# picostepknobs.net
KiCad netlist of a schematic drawn in EAGLE
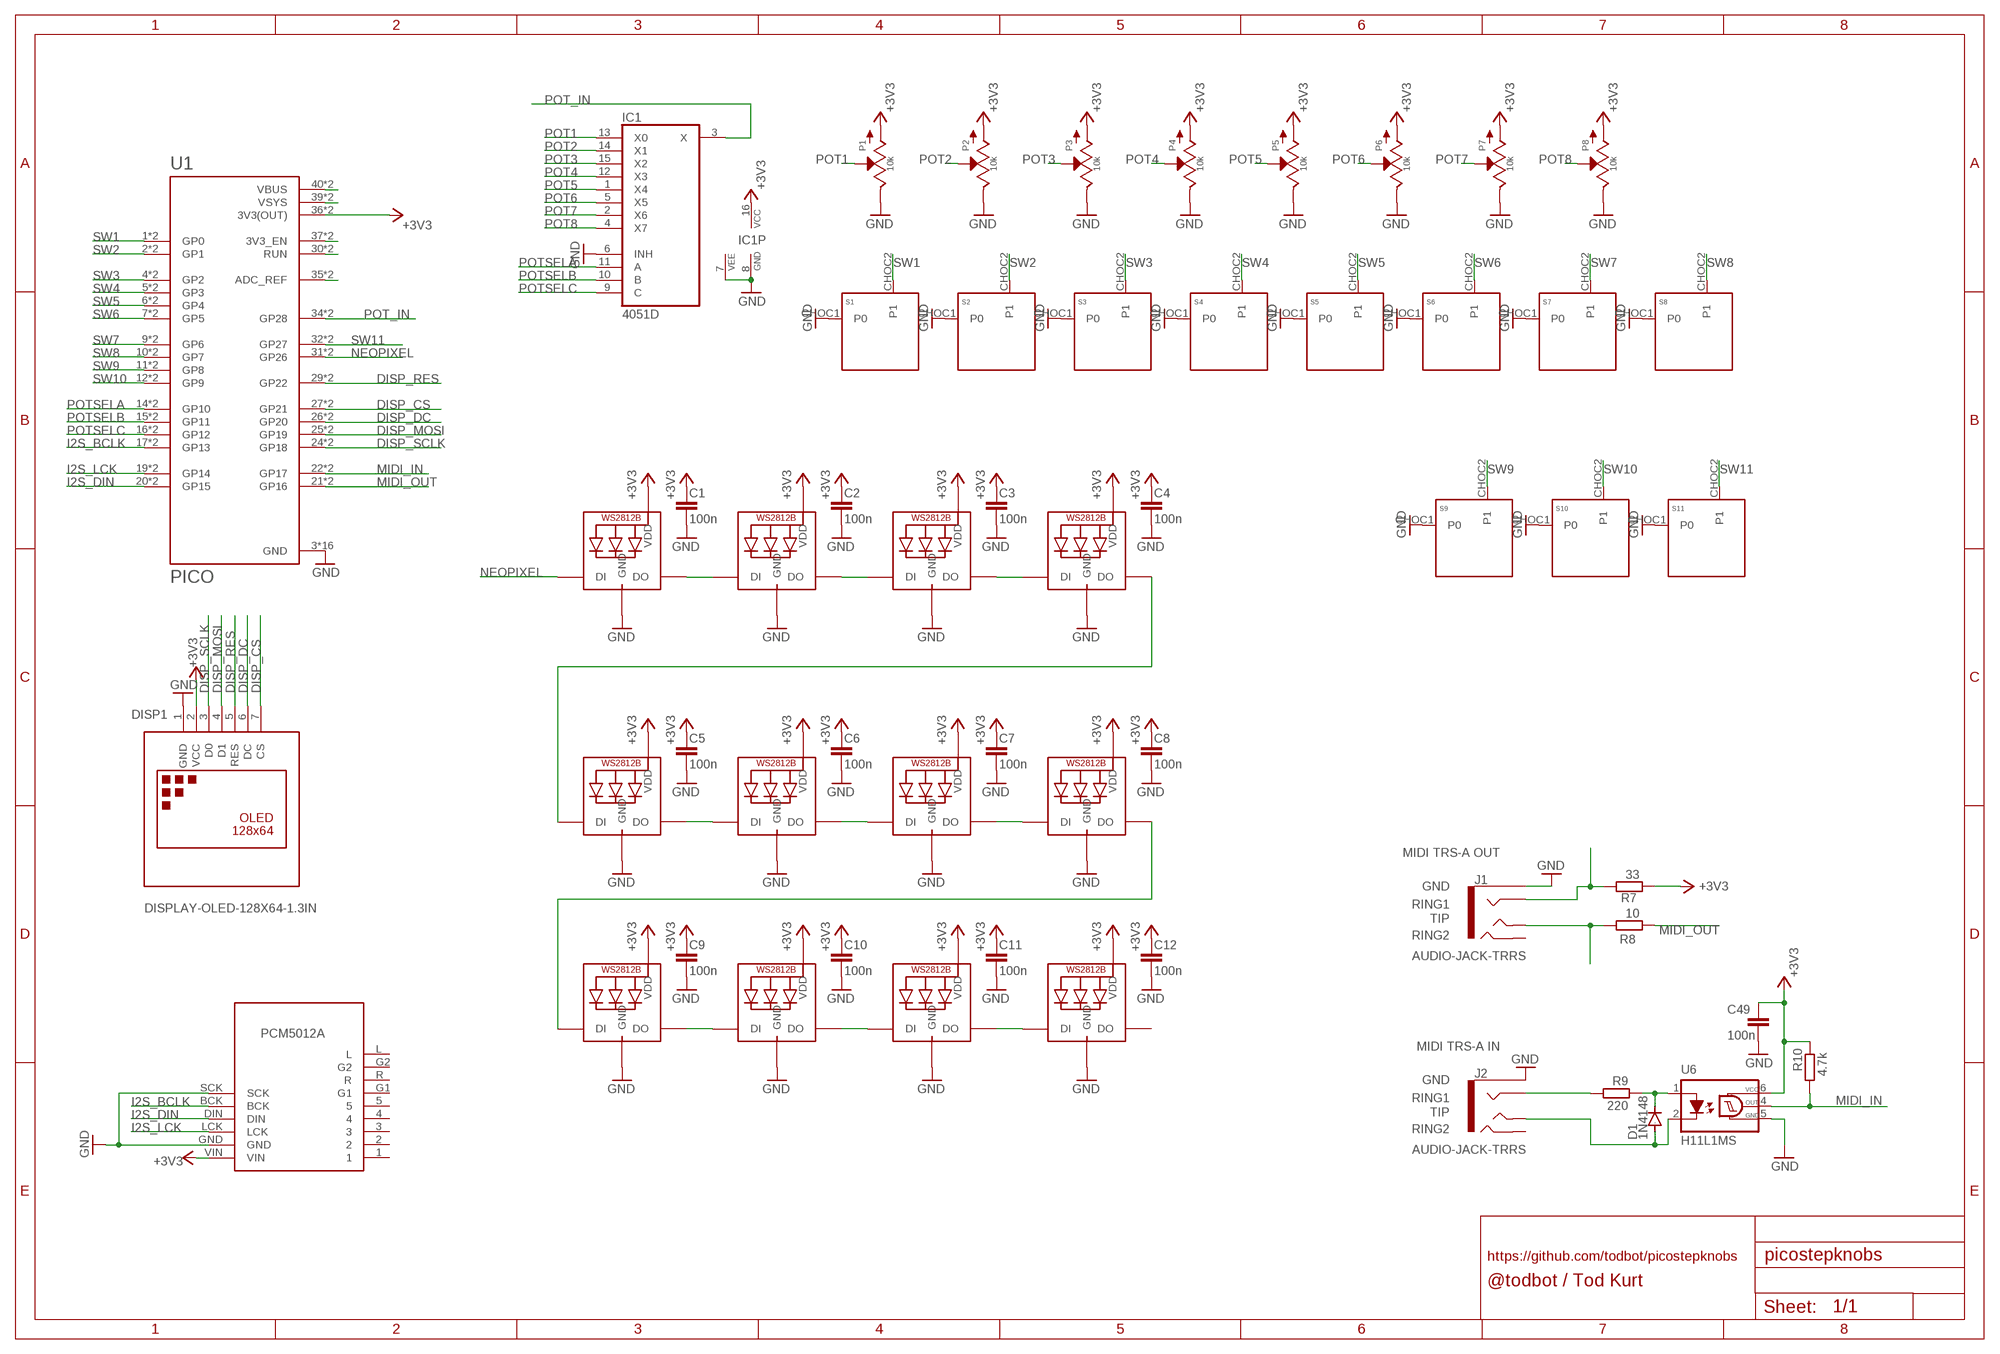
[diagram p0: schematic, sheet 1]

(export (version "E")
  (design (tool "Eeschema 10.0.6"))
  (components
    (comp (ref "C1")
      (value "100n")
      (footprint "eagle-import:C0805")
      (libsource (lib "eagle-import") (part "C-EUC0805"))
    )
    (comp (ref "C2")
      (value "100n")
      (footprint "eagle-import:C0805")
      (libsource (lib "eagle-import") (part "C-EUC0805"))
    )
    (comp (ref "C3")
      (value "100n")
      (footprint "eagle-import:C0805")
      (libsource (lib "eagle-import") (part "C-EUC0805"))
    )
    (comp (ref "C4")
      (value "100n")
      (footprint "eagle-import:C0805")
      (libsource (lib "eagle-import") (part "C-EUC0805"))
    )
    (comp (ref "C5")
      (value "100n")
      (footprint "eagle-import:C0805")
      (libsource (lib "eagle-import") (part "C-EUC0805"))
    )
    (comp (ref "C6")
      (value "100n")
      (footprint "eagle-import:C0805")
      (libsource (lib "eagle-import") (part "C-EUC0805"))
    )
    (comp (ref "C7")
      (value "100n")
      (footprint "eagle-import:C0805")
      (libsource (lib "eagle-import") (part "C-EUC0805"))
    )
    (comp (ref "C8")
      (value "100n")
      (footprint "eagle-import:C0805")
      (libsource (lib "eagle-import") (part "C-EUC0805"))
    )
    (comp (ref "C9")
      (value "100n")
      (footprint "eagle-import:C0805")
      (libsource (lib "eagle-import") (part "C-EUC0805"))
    )
    (comp (ref "C10")
      (value "100n")
      (footprint "eagle-import:C0805")
      (libsource (lib "eagle-import") (part "C-EUC0805"))
    )
    (comp (ref "C11")
      (value "100n")
      (footprint "eagle-import:C0805")
      (libsource (lib "eagle-import") (part "C-EUC0805"))
    )
    (comp (ref "C12")
      (value "100n")
      (footprint "eagle-import:C0805")
      (libsource (lib "eagle-import") (part "C-EUC0805"))
    )
    (comp (ref "C49")
      (value "100n")
      (footprint "eagle-import:C0805")
      (libsource (lib "eagle-import") (part "C-EUC0805"))
    )
    (comp (ref "D1")
      (value "1N4148")
      (footprint "eagle-import:SOD123")
      (libsource (lib "eagle-import") (part "DIODE-SOD123"))
    )
    (comp (ref "DISP1")
      (value "DISPLAY-OLED-128X64-1.3IN")
      (footprint "eagle-import:DISPLAY-OLED-128X64-1.3IN")
      (libsource (lib "eagle-import") (part "DISPLAY-OLED-128X64-1.3IN"))
    )
    (comp (ref "IC1")
      (value "4051D")
      (footprint "eagle-import:SO16")
      (libsource (lib "eagle-import") (part "4051D"))
    )
    (comp (ref "J1")
      (value "AUDIO-JACK-TRRS")
      (footprint "eagle-import:PJ-320D_SPARKFUN")
      (fields (field (name "MPN") "PJ-320D") (field (name "LCSC") "C431535"))
      (libsource (lib "eagle-import") (part "AUDIO-JACK-TRRS"))
    )
    (comp (ref "J2")
      (value "AUDIO-JACK-TRRS")
      (footprint "eagle-import:PJ-320D_SPARKFUN")
      (fields (field (name "MPN") "PJ-320D"))
      (libsource (lib "eagle-import") (part "AUDIO-JACK-TRRS"))
    )
    (comp (ref "LED1")
      (value "WS2812B3535")
      (footprint "eagle-import:LED3535")
      (libsource (lib "eagle-import") (part "WS2812B3535"))
    )
    (comp (ref "LED2")
      (value "WS2812B3535")
      (footprint "eagle-import:LED3535")
      (libsource (lib "eagle-import") (part "WS2812B3535"))
    )
    (comp (ref "LED3")
      (value "WS2812B3535")
      (footprint "eagle-import:LED3535")
      (libsource (lib "eagle-import") (part "WS2812B3535"))
    )
    (comp (ref "LED4")
      (value "WS2812B3535")
      (footprint "eagle-import:LED3535")
      (libsource (lib "eagle-import") (part "WS2812B3535"))
    )
    (comp (ref "LED5")
      (value "WS2812B3535")
      (footprint "eagle-import:LED3535")
      (libsource (lib "eagle-import") (part "WS2812B3535"))
    )
    (comp (ref "LED6")
      (value "WS2812B3535")
      (footprint "eagle-import:LED3535")
      (libsource (lib "eagle-import") (part "WS2812B3535"))
    )
    (comp (ref "LED7")
      (value "WS2812B3535")
      (footprint "eagle-import:LED3535")
      (libsource (lib "eagle-import") (part "WS2812B3535"))
    )
    (comp (ref "LED8")
      (value "WS2812B3535")
      (footprint "eagle-import:LED3535")
      (libsource (lib "eagle-import") (part "WS2812B3535"))
    )
    (comp (ref "LED9")
      (value "WS2812B3535")
      (footprint "eagle-import:LED3535")
      (libsource (lib "eagle-import") (part "WS2812B3535"))
    )
    (comp (ref "LED10")
      (value "WS2812B3535")
      (footprint "eagle-import:LED3535")
      (libsource (lib "eagle-import") (part "WS2812B3535"))
    )
    (comp (ref "LED11")
      (value "WS2812B3535")
      (footprint "eagle-import:LED3535")
      (libsource (lib "eagle-import") (part "WS2812B3535"))
    )
    (comp (ref "LED12")
      (value "WS2812B3535")
      (footprint "eagle-import:LED3535")
      (libsource (lib "eagle-import") (part "WS2812B3535"))
    )
    (comp (ref "P1")
      (value "10k")
      (footprint "eagle-import:OG-POTS_ALPS_POT_VERTICAL_WITHBIGKNOB")
      (libsource (lib "eagle-import") (part "POTZEPHPOT_BIGKNOB"))
    )
    (comp (ref "P2")
      (value "10k")
      (footprint "eagle-import:OG-POTS_ALPS_POT_VERTICAL_WITHBIGKNOB")
      (libsource (lib "eagle-import") (part "POTZEPHPOT_BIGKNOB"))
    )
    (comp (ref "P3")
      (value "10k")
      (footprint "eagle-import:OG-POTS_ALPS_POT_VERTICAL_WITHBIGKNOB")
      (libsource (lib "eagle-import") (part "POTZEPHPOT_BIGKNOB"))
    )
    (comp (ref "P4")
      (value "10k")
      (footprint "eagle-import:OG-POTS_ALPS_POT_VERTICAL_WITHBIGKNOB")
      (libsource (lib "eagle-import") (part "POTZEPHPOT_BIGKNOB"))
    )
    (comp (ref "P5")
      (value "10k")
      (footprint "eagle-import:OG-POTS_ALPS_POT_VERTICAL_WITHBIGKNOB")
      (libsource (lib "eagle-import") (part "POTZEPHPOT_BIGKNOB"))
    )
    (comp (ref "P6")
      (value "10k")
      (footprint "eagle-import:OG-POTS_ALPS_POT_VERTICAL_WITHBIGKNOB")
      (libsource (lib "eagle-import") (part "POTZEPHPOT_BIGKNOB"))
    )
    (comp (ref "P7")
      (value "10k")
      (footprint "eagle-import:OG-POTS_ALPS_POT_VERTICAL_WITHBIGKNOB")
      (libsource (lib "eagle-import") (part "POTZEPHPOT_BIGKNOB"))
    )
    (comp (ref "P8")
      (value "10k")
      (footprint "eagle-import:OG-POTS_ALPS_POT_VERTICAL_WITHBIGKNOB")
      (libsource (lib "eagle-import") (part "POTZEPHPOT_BIGKNOB"))
    )
    (comp (ref "PCM5102A")
      (value "I2S_PCM_51XX_SOUNDCARD")
      (footprint "eagle-import:I2S_PCM_5100_SOUNDCARD")
      (libsource (lib "eagle-import") (part "I2S_PCM_51XX_SOUNDCARD"))
    )
    (comp (ref "R7")
      (value "33")
      (footprint "eagle-import:R0805")
      (libsource (lib "eagle-import") (part "R-EU_R0805"))
    )
    (comp (ref "R8")
      (value "10")
      (footprint "eagle-import:R0805")
      (libsource (lib "eagle-import") (part "R-EU_R0805"))
    )
    (comp (ref "R9")
      (value "220")
      (footprint "eagle-import:R0805")
      (libsource (lib "eagle-import") (part "R-EU_R0805"))
    )
    (comp (ref "R10")
      (value "4.7k")
      (footprint "eagle-import:R0805")
      (libsource (lib "eagle-import") (part "R-EU_R0805"))
    )
    (comp (ref "S1")
      (value "KEYSWITCH-PLAIN-CHOC-1U")
      (footprint "eagle-import:CHOC-1U")
      (libsource (lib "eagle-import") (part "KEYSWITCH-PLAIN-CHOC-1U"))
    )
    (comp (ref "S2")
      (value "KEYSWITCH-PLAIN-CHOC-1U")
      (footprint "eagle-import:CHOC-1U")
      (libsource (lib "eagle-import") (part "KEYSWITCH-PLAIN-CHOC-1U"))
    )
    (comp (ref "S3")
      (value "KEYSWITCH-PLAIN-CHOC-1U")
      (footprint "eagle-import:CHOC-1U")
      (libsource (lib "eagle-import") (part "KEYSWITCH-PLAIN-CHOC-1U"))
    )
    (comp (ref "S4")
      (value "KEYSWITCH-PLAIN-CHOC-1U")
      (footprint "eagle-import:CHOC-1U")
      (libsource (lib "eagle-import") (part "KEYSWITCH-PLAIN-CHOC-1U"))
    )
    (comp (ref "S5")
      (value "KEYSWITCH-PLAIN-CHOC-1U")
      (footprint "eagle-import:CHOC-1U")
      (libsource (lib "eagle-import") (part "KEYSWITCH-PLAIN-CHOC-1U"))
    )
    (comp (ref "S6")
      (value "KEYSWITCH-PLAIN-CHOC-1U")
      (footprint "eagle-import:CHOC-1U")
      (libsource (lib "eagle-import") (part "KEYSWITCH-PLAIN-CHOC-1U"))
    )
    (comp (ref "S7")
      (value "KEYSWITCH-PLAIN-CHOC-1U")
      (footprint "eagle-import:CHOC-1U")
      (libsource (lib "eagle-import") (part "KEYSWITCH-PLAIN-CHOC-1U"))
    )
    (comp (ref "S8")
      (value "KEYSWITCH-PLAIN-CHOC-1U")
      (footprint "eagle-import:CHOC-1U")
      (libsource (lib "eagle-import") (part "KEYSWITCH-PLAIN-CHOC-1U"))
    )
    (comp (ref "S9")
      (value "KEYSWITCH-PLAIN-CHOC-1U")
      (footprint "eagle-import:CHOC-1U")
      (libsource (lib "eagle-import") (part "KEYSWITCH-PLAIN-CHOC-1U"))
    )
    (comp (ref "S10")
      (value "KEYSWITCH-PLAIN-CHOC-1U")
      (footprint "eagle-import:CHOC-1U")
      (libsource (lib "eagle-import") (part "KEYSWITCH-PLAIN-CHOC-1U"))
    )
    (comp (ref "S11")
      (value "KEYSWITCH-PLAIN-CHOC-1U")
      (footprint "eagle-import:CHOC-1U")
      (libsource (lib "eagle-import") (part "KEYSWITCH-PLAIN-CHOC-1U"))
    )
    (comp (ref "U1")
      (value "PICO")
      (footprint "eagle-import:PICO-PKG-NO_DEBUG")
      (libsource (lib "eagle-import") (part "RASPBERRY_PICO-NO_DEBUG"))
    )
    (comp (ref "U6")
      (value "H11L1MS")
      (footprint "eagle-import:DIL6-SMD")
      (libsource (lib "eagle-import") (part "H11LMS1"))
    )
  )
  (nets
    (net (code "1") (name "+3V3") (class "Default")
      (node (ref "C1") (pin "1") (pinfunction "1_1") (pintype "passive"))
      (node (ref "C10") (pin "1") (pinfunction "1_1") (pintype "passive"))
      (node (ref "C11") (pin "1") (pinfunction "1_1") (pintype "passive"))
      (node (ref "C12") (pin "1") (pinfunction "1_1") (pintype "passive"))
      (node (ref "C2") (pin "1") (pinfunction "1_1") (pintype "passive"))
      (node (ref "C3") (pin "1") (pinfunction "1_1") (pintype "passive"))
      (node (ref "C4") (pin "1") (pinfunction "1_1") (pintype "passive"))
      (node (ref "C49") (pin "1") (pinfunction "1_1") (pintype "passive"))
      (node (ref "C5") (pin "1") (pinfunction "1_1") (pintype "passive"))
      (node (ref "C6") (pin "1") (pinfunction "1_1") (pintype "passive"))
      (node (ref "C7") (pin "1") (pinfunction "1_1") (pintype "passive"))
      (node (ref "C8") (pin "1") (pinfunction "1_1") (pintype "passive"))
      (node (ref "C9") (pin "1") (pinfunction "1_1") (pintype "passive"))
      (node (ref "DISP1") (pin "2") (pinfunction "VCC_2") (pintype "power_in"))
      (node (ref "IC1") (pin "16") (pinfunction "VCC_16") (pintype "power_in"))
      (node (ref "LED1") (pin "2") (pinfunction "VDD_2") (pintype "power_in"))
      (node (ref "LED10") (pin "2") (pinfunction "VDD_2") (pintype "power_in"))
      (node (ref "LED11") (pin "2") (pinfunction "VDD_2") (pintype "power_in"))
      (node (ref "LED12") (pin "2") (pinfunction "VDD_2") (pintype "power_in"))
      (node (ref "LED2") (pin "2") (pinfunction "VDD_2") (pintype "power_in"))
      (node (ref "LED3") (pin "2") (pinfunction "VDD_2") (pintype "power_in"))
      (node (ref "LED4") (pin "2") (pinfunction "VDD_2") (pintype "power_in"))
      (node (ref "LED5") (pin "2") (pinfunction "VDD_2") (pintype "power_in"))
      (node (ref "LED6") (pin "2") (pinfunction "VDD_2") (pintype "power_in"))
      (node (ref "LED7") (pin "2") (pinfunction "VDD_2") (pintype "power_in"))
      (node (ref "LED8") (pin "2") (pinfunction "VDD_2") (pintype "power_in"))
      (node (ref "LED9") (pin "2") (pinfunction "VDD_2") (pintype "power_in"))
      (node (ref "P1") (pin "P$3") (pinfunction "A_P$3") (pintype "passive"))
      (node (ref "P2") (pin "P$3") (pinfunction "A_P$3") (pintype "passive"))
      (node (ref "P3") (pin "P$3") (pinfunction "A_P$3") (pintype "passive"))
      (node (ref "P4") (pin "P$3") (pinfunction "A_P$3") (pintype "passive"))
      (node (ref "P5") (pin "P$3") (pinfunction "A_P$3") (pintype "passive"))
      (node (ref "P6") (pin "P$3") (pinfunction "A_P$3") (pintype "passive"))
      (node (ref "P7") (pin "P$3") (pinfunction "A_P$3") (pintype "passive"))
      (node (ref "P8") (pin "P$3") (pinfunction "A_P$3") (pintype "passive"))
      (node (ref "PCM5102A") (pin "VIN") (pinfunction "VIN_VIN") (pintype "bidirectional"))
      (node (ref "R10") (pin "1") (pinfunction "1_1") (pintype "passive"))
      (node (ref "R7") (pin "2") (pinfunction "2_2") (pintype "passive"))
      (node (ref "U1") (pin "36") (pinfunction "3V3(OUT)_36") (pintype "power_in"))
      (node (ref "U1") (pin "P$36") (pinfunction "3V3(OUT)_P$36") (pintype "power_in"))
      (node (ref "U6") (pin "6") (pinfunction "VCC_6") (pintype "power_in"))
    )
    (net (code "2") (name "/DISP_CS") (class "Default")
      (node (ref "DISP1") (pin "7") (pinfunction "CS_7") (pintype "bidirectional"))
      (node (ref "U1") (pin "27") (pinfunction "GP21_27") (pintype "bidirectional"))
      (node (ref "U1") (pin "P$27") (pinfunction "GP21_P$27") (pintype "bidirectional"))
    )
    (net (code "3") (name "/DISP_DC") (class "Default")
      (node (ref "DISP1") (pin "6") (pinfunction "DC_6") (pintype "bidirectional"))
      (node (ref "U1") (pin "26") (pinfunction "GP20_26") (pintype "bidirectional"))
      (node (ref "U1") (pin "P$26") (pinfunction "GP20_P$26") (pintype "bidirectional"))
    )
    (net (code "4") (name "/DISP_MOSI") (class "Default")
      (node (ref "DISP1") (pin "4") (pinfunction "D1_4") (pintype "bidirectional"))
      (node (ref "U1") (pin "25") (pinfunction "GP19_25") (pintype "bidirectional"))
      (node (ref "U1") (pin "P$25") (pinfunction "GP19_P$25") (pintype "bidirectional"))
    )
    (net (code "5") (name "/DISP_RES") (class "Default")
      (node (ref "DISP1") (pin "5") (pinfunction "RES_5") (pintype "bidirectional"))
      (node (ref "U1") (pin "29") (pinfunction "GP22_29") (pintype "bidirectional"))
      (node (ref "U1") (pin "P$29") (pinfunction "GP22_P$29") (pintype "bidirectional"))
    )
    (net (code "6") (name "/DISP_SCLK") (class "Default")
      (node (ref "DISP1") (pin "3") (pinfunction "D0_3") (pintype "bidirectional"))
      (node (ref "U1") (pin "24") (pinfunction "GP18_24") (pintype "bidirectional"))
      (node (ref "U1") (pin "P$24") (pinfunction "GP18_P$24") (pintype "bidirectional"))
    )
    (net (code "7") (name "/I2S_BCLK") (class "Default")
      (node (ref "PCM5102A") (pin "BCK") (pinfunction "BCK_BCK") (pintype "bidirectional"))
      (node (ref "U1") (pin "17") (pinfunction "GP13_17") (pintype "bidirectional"))
      (node (ref "U1") (pin "P$17") (pinfunction "GP13_P$17") (pintype "bidirectional"))
    )
    (net (code "8") (name "/I2S_DIN") (class "Default")
      (node (ref "PCM5102A") (pin "DIN") (pinfunction "DIN_DIN") (pintype "bidirectional"))
      (node (ref "U1") (pin "20") (pinfunction "GP15_20") (pintype "bidirectional"))
      (node (ref "U1") (pin "P$20") (pinfunction "GP15_P$20") (pintype "bidirectional"))
    )
    (net (code "9") (name "/I2S_LCK") (class "Default")
      (node (ref "PCM5102A") (pin "LCK") (pinfunction "LCK_LCK") (pintype "bidirectional"))
      (node (ref "U1") (pin "19") (pinfunction "GP14_19") (pintype "bidirectional"))
      (node (ref "U1") (pin "P$19") (pinfunction "GP14_P$19") (pintype "bidirectional"))
    )
    (net (code "10") (name "/MIDI_IN") (class "Default")
      (node (ref "R10") (pin "2") (pinfunction "2_2") (pintype "passive"))
      (node (ref "U1") (pin "22") (pinfunction "GP17_22") (pintype "bidirectional"))
      (node (ref "U1") (pin "P$22") (pinfunction "GP17_P$22") (pintype "bidirectional"))
      (node (ref "U6") (pin "4") (pinfunction "OUT_4") (pintype "output"))
    )
    (net (code "11") (name "/MIDI_OUT") (class "Default")
      (node (ref "R8") (pin "2") (pinfunction "2_2") (pintype "passive"))
      (node (ref "U1") (pin "21") (pinfunction "GP16_21") (pintype "bidirectional"))
      (node (ref "U1") (pin "P$21") (pinfunction "GP16_P$21") (pintype "bidirectional"))
    )
    (net (code "12") (name "/NEOPIXEL") (class "Default")
      (node (ref "LED1") (pin "1") (pinfunction "DI_1") (pintype "input"))
      (node (ref "U1") (pin "31") (pinfunction "GP26_31") (pintype "bidirectional"))
      (node (ref "U1") (pin "P$31") (pinfunction "GP26_P$31") (pintype "bidirectional"))
    )
    (net (code "13") (name "/POT1") (class "Default")
      (node (ref "IC1") (pin "13") (pinfunction "X0_13") (pintype "bidirectional"))
      (node (ref "P1") (pin "P$2") (pinfunction "S_P$2") (pintype "passive"))
    )
    (net (code "14") (name "/POT2") (class "Default")
      (node (ref "IC1") (pin "14") (pinfunction "X1_14") (pintype "bidirectional"))
      (node (ref "P2") (pin "P$2") (pinfunction "S_P$2") (pintype "passive"))
    )
    (net (code "15") (name "/POT3") (class "Default")
      (node (ref "IC1") (pin "15") (pinfunction "X2_15") (pintype "bidirectional"))
      (node (ref "P3") (pin "P$2") (pinfunction "S_P$2") (pintype "passive"))
    )
    (net (code "16") (name "/POT4") (class "Default")
      (node (ref "IC1") (pin "12") (pinfunction "X3_12") (pintype "bidirectional"))
      (node (ref "P4") (pin "P$2") (pinfunction "S_P$2") (pintype "passive"))
    )
    (net (code "17") (name "/POT5") (class "Default")
      (node (ref "IC1") (pin "1") (pinfunction "X4_1") (pintype "bidirectional"))
      (node (ref "P5") (pin "P$2") (pinfunction "S_P$2") (pintype "passive"))
    )
    (net (code "18") (name "/POT6") (class "Default")
      (node (ref "IC1") (pin "5") (pinfunction "X5_5") (pintype "bidirectional"))
      (node (ref "P6") (pin "P$2") (pinfunction "S_P$2") (pintype "passive"))
    )
    (net (code "19") (name "/POT7") (class "Default")
      (node (ref "IC1") (pin "2") (pinfunction "X6_2") (pintype "bidirectional"))
      (node (ref "P7") (pin "P$2") (pinfunction "S_P$2") (pintype "passive"))
    )
    (net (code "20") (name "/POT8") (class "Default")
      (node (ref "IC1") (pin "4") (pinfunction "X7_4") (pintype "bidirectional"))
      (node (ref "P8") (pin "P$2") (pinfunction "S_P$2") (pintype "passive"))
    )
    (net (code "21") (name "/POTSELA") (class "Default")
      (node (ref "IC1") (pin "11") (pinfunction "A_11") (pintype "input"))
      (node (ref "U1") (pin "14") (pinfunction "GP10_14") (pintype "bidirectional"))
      (node (ref "U1") (pin "P$14") (pinfunction "GP10_P$14") (pintype "bidirectional"))
    )
    (net (code "22") (name "/POTSELB") (class "Default")
      (node (ref "IC1") (pin "10") (pinfunction "B_10") (pintype "input"))
      (node (ref "U1") (pin "15") (pinfunction "GP11_15") (pintype "bidirectional"))
      (node (ref "U1") (pin "P$15") (pinfunction "GP11_P$15") (pintype "bidirectional"))
    )
    (net (code "23") (name "/POTSELC") (class "Default")
      (node (ref "IC1") (pin "9") (pinfunction "C_9") (pintype "input"))
      (node (ref "U1") (pin "16") (pinfunction "GP12_16") (pintype "bidirectional"))
      (node (ref "U1") (pin "P$16") (pinfunction "GP12_P$16") (pintype "bidirectional"))
    )
    (net (code "24") (name "/POT_IN") (class "Default")
      (node (ref "IC1") (pin "3") (pinfunction "X_3") (pintype "bidirectional"))
      (node (ref "U1") (pin "34") (pinfunction "GP28_34") (pintype "bidirectional"))
      (node (ref "U1") (pin "P$34") (pinfunction "GP28_P$34") (pintype "bidirectional"))
    )
    (net (code "25") (name "/SW1") (class "Default")
      (node (ref "S1") (pin "CHOC2") (pinfunction "P1_CHOC2") (pintype "bidirectional"))
      (node (ref "U1") (pin "1") (pinfunction "GP0_1") (pintype "bidirectional"))
      (node (ref "U1") (pin "P$1") (pinfunction "GP0_P$1") (pintype "bidirectional"))
    )
    (net (code "26") (name "/SW2") (class "Default")
      (node (ref "S2") (pin "CHOC2") (pinfunction "P1_CHOC2") (pintype "bidirectional"))
      (node (ref "U1") (pin "2") (pinfunction "GP1_2") (pintype "bidirectional"))
      (node (ref "U1") (pin "P$2") (pinfunction "GP1_P$2") (pintype "bidirectional"))
    )
    (net (code "27") (name "/SW3") (class "Default")
      (node (ref "S3") (pin "CHOC2") (pinfunction "P1_CHOC2") (pintype "bidirectional"))
      (node (ref "U1") (pin "4") (pinfunction "GP2_4") (pintype "bidirectional"))
      (node (ref "U1") (pin "P$4") (pinfunction "GP2_P$4") (pintype "bidirectional"))
    )
    (net (code "28") (name "/SW4") (class "Default")
      (node (ref "S4") (pin "CHOC2") (pinfunction "P1_CHOC2") (pintype "bidirectional"))
      (node (ref "U1") (pin "5") (pinfunction "GP3_5") (pintype "bidirectional"))
      (node (ref "U1") (pin "P$5") (pinfunction "GP3_P$5") (pintype "bidirectional"))
    )
    (net (code "29") (name "/SW5") (class "Default")
      (node (ref "S5") (pin "CHOC2") (pinfunction "P1_CHOC2") (pintype "bidirectional"))
      (node (ref "U1") (pin "6") (pinfunction "GP4_6") (pintype "bidirectional"))
      (node (ref "U1") (pin "P$6") (pinfunction "GP4_P$6") (pintype "bidirectional"))
    )
    (net (code "30") (name "/SW6") (class "Default")
      (node (ref "S6") (pin "CHOC2") (pinfunction "P1_CHOC2") (pintype "bidirectional"))
      (node (ref "U1") (pin "7") (pinfunction "GP5_7") (pintype "bidirectional"))
      (node (ref "U1") (pin "P$7") (pinfunction "GP5_P$7") (pintype "bidirectional"))
    )
    (net (code "31") (name "/SW7") (class "Default")
      (node (ref "S7") (pin "CHOC2") (pinfunction "P1_CHOC2") (pintype "bidirectional"))
      (node (ref "U1") (pin "9") (pinfunction "GP6_9") (pintype "bidirectional"))
      (node (ref "U1") (pin "P$9") (pinfunction "GP6_P$9") (pintype "bidirectional"))
    )
    (net (code "32") (name "/SW8") (class "Default")
      (node (ref "S8") (pin "CHOC2") (pinfunction "P1_CHOC2") (pintype "bidirectional"))
      (node (ref "U1") (pin "10") (pinfunction "GP7_10") (pintype "bidirectional"))
      (node (ref "U1") (pin "P$10") (pinfunction "GP7_P$10") (pintype "bidirectional"))
    )
    (net (code "33") (name "/SW9") (class "Default")
      (node (ref "S9") (pin "CHOC2") (pinfunction "P1_CHOC2") (pintype "bidirectional"))
      (node (ref "U1") (pin "11") (pinfunction "GP8_11") (pintype "bidirectional"))
      (node (ref "U1") (pin "P$11") (pinfunction "GP8_P$11") (pintype "bidirectional"))
    )
    (net (code "34") (name "/SW10") (class "Default")
      (node (ref "S10") (pin "CHOC2") (pinfunction "P1_CHOC2") (pintype "bidirectional"))
      (node (ref "U1") (pin "12") (pinfunction "GP9_12") (pintype "bidirectional"))
      (node (ref "U1") (pin "P$12") (pinfunction "GP9_P$12") (pintype "bidirectional"))
    )
    (net (code "35") (name "/SW11") (class "Default")
      (node (ref "S11") (pin "CHOC2") (pinfunction "P1_CHOC2") (pintype "bidirectional"))
      (node (ref "U1") (pin "32") (pinfunction "GP27_32") (pintype "bidirectional"))
      (node (ref "U1") (pin "P$32") (pinfunction "GP27_P$32") (pintype "bidirectional"))
    )
    (net (code "36") (name "GND") (class "Default")
      (node (ref "C1") (pin "2") (pinfunction "2_2") (pintype "passive"))
      (node (ref "C10") (pin "2") (pinfunction "2_2") (pintype "passive"))
      (node (ref "C11") (pin "2") (pinfunction "2_2") (pintype "passive"))
      (node (ref "C12") (pin "2") (pinfunction "2_2") (pintype "passive"))
      (node (ref "C2") (pin "2") (pinfunction "2_2") (pintype "passive"))
      (node (ref "C3") (pin "2") (pinfunction "2_2") (pintype "passive"))
      (node (ref "C4") (pin "2") (pinfunction "2_2") (pintype "passive"))
      (node (ref "C49") (pin "2") (pinfunction "2_2") (pintype "passive"))
      (node (ref "C5") (pin "2") (pinfunction "2_2") (pintype "passive"))
      (node (ref "C6") (pin "2") (pinfunction "2_2") (pintype "passive"))
      (node (ref "C7") (pin "2") (pinfunction "2_2") (pintype "passive"))
      (node (ref "C8") (pin "2") (pinfunction "2_2") (pintype "passive"))
      (node (ref "C9") (pin "2") (pinfunction "2_2") (pintype "passive"))
      (node (ref "DISP1") (pin "1") (pinfunction "GND_1") (pintype "power_in"))
      (node (ref "IC1") (pin "6") (pinfunction "INH_6") (pintype "input"))
      (node (ref "IC1") (pin "7") (pinfunction "VEE_7") (pintype "power_in"))
      (node (ref "IC1") (pin "8") (pinfunction "GND_8") (pintype "power_in"))
      (node (ref "J1") (pin "EARTH") (pinfunction "EARTH_EARTH") (pintype "bidirectional"))
      (node (ref "J2") (pin "EARTH") (pinfunction "EARTH_EARTH") (pintype "bidirectional"))
      (node (ref "LED1") (pin "4") (pinfunction "GND_4") (pintype "power_in"))
      (node (ref "LED10") (pin "4") (pinfunction "GND_4") (pintype "power_in"))
      (node (ref "LED11") (pin "4") (pinfunction "GND_4") (pintype "power_in"))
      (node (ref "LED12") (pin "4") (pinfunction "GND_4") (pintype "power_in"))
      (node (ref "LED2") (pin "4") (pinfunction "GND_4") (pintype "power_in"))
      (node (ref "LED3") (pin "4") (pinfunction "GND_4") (pintype "power_in"))
      (node (ref "LED4") (pin "4") (pinfunction "GND_4") (pintype "power_in"))
      (node (ref "LED5") (pin "4") (pinfunction "GND_4") (pintype "power_in"))
      (node (ref "LED6") (pin "4") (pinfunction "GND_4") (pintype "power_in"))
      (node (ref "LED7") (pin "4") (pinfunction "GND_4") (pintype "power_in"))
      (node (ref "LED8") (pin "4") (pinfunction "GND_4") (pintype "power_in"))
      (node (ref "LED9") (pin "4") (pinfunction "GND_4") (pintype "power_in"))
      (node (ref "P1") (pin "P$1") (pinfunction "E_P$1") (pintype "passive"))
      (node (ref "P2") (pin "P$1") (pinfunction "E_P$1") (pintype "passive"))
      (node (ref "P3") (pin "P$1") (pinfunction "E_P$1") (pintype "passive"))
      (node (ref "P4") (pin "P$1") (pinfunction "E_P$1") (pintype "passive"))
      (node (ref "P5") (pin "P$1") (pinfunction "E_P$1") (pintype "passive"))
      (node (ref "P6") (pin "P$1") (pinfunction "E_P$1") (pintype "passive"))
      (node (ref "P7") (pin "P$1") (pinfunction "E_P$1") (pintype "passive"))
      (node (ref "P8") (pin "P$1") (pinfunction "E_P$1") (pintype "passive"))
      (node (ref "PCM5102A") (pin "GND") (pinfunction "GND_GND") (pintype "bidirectional"))
      (node (ref "PCM5102A") (pin "SCK") (pinfunction "SCK_SCK") (pintype "bidirectional"))
      (node (ref "S1") (pin "CHOC1") (pinfunction "P0_CHOC1") (pintype "bidirectional"))
      (node (ref "S10") (pin "CHOC1") (pinfunction "P0_CHOC1") (pintype "bidirectional"))
      (node (ref "S11") (pin "CHOC1") (pinfunction "P0_CHOC1") (pintype "bidirectional"))
      (node (ref "S2") (pin "CHOC1") (pinfunction "P0_CHOC1") (pintype "bidirectional"))
      (node (ref "S3") (pin "CHOC1") (pinfunction "P0_CHOC1") (pintype "bidirectional"))
      (node (ref "S4") (pin "CHOC1") (pinfunction "P0_CHOC1") (pintype "bidirectional"))
      (node (ref "S5") (pin "CHOC1") (pinfunction "P0_CHOC1") (pintype "bidirectional"))
      (node (ref "S6") (pin "CHOC1") (pinfunction "P0_CHOC1") (pintype "bidirectional"))
      (node (ref "S7") (pin "CHOC1") (pinfunction "P0_CHOC1") (pintype "bidirectional"))
      (node (ref "S8") (pin "CHOC1") (pinfunction "P0_CHOC1") (pintype "bidirectional"))
      (node (ref "S9") (pin "CHOC1") (pinfunction "P0_CHOC1") (pintype "bidirectional"))
      (node (ref "U1") (pin "13") (pinfunction "GND_13") (pintype "power_in"))
      (node (ref "U1") (pin "18") (pinfunction "GND_18") (pintype "power_in"))
      (node (ref "U1") (pin "23") (pinfunction "GND_23") (pintype "power_in"))
      (node (ref "U1") (pin "28") (pinfunction "GND_28") (pintype "power_in"))
      (node (ref "U1") (pin "3") (pinfunction "GND_3") (pintype "power_in"))
      (node (ref "U1") (pin "33") (pinfunction "GND_33") (pintype "power_in"))
      (node (ref "U1") (pin "38") (pinfunction "GND_38") (pintype "power_in"))
      (node (ref "U1") (pin "8") (pinfunction "GND_8") (pintype "power_in"))
      (node (ref "U1") (pin "P$13") (pinfunction "GND_P$13") (pintype "power_in"))
      (node (ref "U1") (pin "P$18") (pinfunction "GND_P$18") (pintype "power_in"))
      (node (ref "U1") (pin "P$23") (pinfunction "GND_P$23") (pintype "power_in"))
      (node (ref "U1") (pin "P$28") (pinfunction "GND_P$28") (pintype "power_in"))
      (node (ref "U1") (pin "P$3") (pinfunction "GND_P$3") (pintype "power_in"))
      (node (ref "U1") (pin "P$33") (pinfunction "GND_P$33") (pintype "power_in"))
      (node (ref "U1") (pin "P$38") (pinfunction "GND_P$38") (pintype "power_in"))
      (node (ref "U1") (pin "P$8") (pinfunction "GND_P$8") (pintype "power_in"))
      (node (ref "U6") (pin "5") (pinfunction "GND_5") (pintype "power_in"))
    )
    (net (code "37") (name "Net-(J1-PadRING1)") (class "Default")
      (node (ref "J1") (pin "RING1") (pinfunction "RING1_RING1") (pintype "bidirectional"))
      (node (ref "R7") (pin "1") (pinfunction "1_1") (pintype "passive"))
    )
    (net (code "38") (name "Net-(J1-PadTIP)") (class "Default")
      (node (ref "J1") (pin "TIP") (pinfunction "TIP_TIP") (pintype "bidirectional"))
      (node (ref "R8") (pin "1") (pinfunction "1_1") (pintype "passive"))
    )
    (net (code "39") (name "Net-(J2-PadRING1)") (class "Default")
      (node (ref "J2") (pin "RING1") (pinfunction "RING1_RING1") (pintype "bidirectional"))
      (node (ref "R9") (pin "2") (pinfunction "2_2") (pintype "passive"))
    )
    (net (code "40") (name "Net-(LED1-DO)") (class "Default")
      (node (ref "LED1") (pin "3") (pinfunction "DO_3") (pintype "output"))
      (node (ref "LED2") (pin "1") (pinfunction "DI_1") (pintype "input"))
    )
    (net (code "41") (name "Net-(LED2-DO)") (class "Default")
      (node (ref "LED2") (pin "3") (pinfunction "DO_3") (pintype "output"))
      (node (ref "LED3") (pin "1") (pinfunction "DI_1") (pintype "input"))
    )
    (net (code "42") (name "Net-(LED3-DO)") (class "Default")
      (node (ref "LED3") (pin "3") (pinfunction "DO_3") (pintype "output"))
      (node (ref "LED4") (pin "1") (pinfunction "DI_1") (pintype "input"))
    )
    (net (code "43") (name "Net-(LED4-DO)") (class "Default")
      (node (ref "LED4") (pin "3") (pinfunction "DO_3") (pintype "output"))
      (node (ref "LED5") (pin "1") (pinfunction "DI_1") (pintype "input"))
    )
    (net (code "44") (name "Net-(LED5-DO)") (class "Default")
      (node (ref "LED5") (pin "3") (pinfunction "DO_3") (pintype "output"))
      (node (ref "LED6") (pin "1") (pinfunction "DI_1") (pintype "input"))
    )
    (net (code "45") (name "Net-(LED6-DO)") (class "Default")
      (node (ref "LED6") (pin "3") (pinfunction "DO_3") (pintype "output"))
      (node (ref "LED7") (pin "1") (pinfunction "DI_1") (pintype "input"))
    )
    (net (code "46") (name "Net-(LED7-DO)") (class "Default")
      (node (ref "LED7") (pin "3") (pinfunction "DO_3") (pintype "output"))
      (node (ref "LED8") (pin "1") (pinfunction "DI_1") (pintype "input"))
    )
    (net (code "47") (name "Net-(LED8-DO)") (class "Default")
      (node (ref "LED8") (pin "3") (pinfunction "DO_3") (pintype "output"))
      (node (ref "LED9") (pin "1") (pinfunction "DI_1") (pintype "input"))
    )
    (net (code "48") (name "Net-(LED10-DI)") (class "Default")
      (node (ref "LED10") (pin "1") (pinfunction "DI_1") (pintype "input"))
      (node (ref "LED9") (pin "3") (pinfunction "DO_3") (pintype "output"))
    )
    (net (code "49") (name "Net-(LED10-DO)") (class "Default")
      (node (ref "LED10") (pin "3") (pinfunction "DO_3") (pintype "output"))
      (node (ref "LED11") (pin "1") (pinfunction "DI_1") (pintype "input"))
    )
    (net (code "50") (name "Net-(LED11-DO)") (class "Default")
      (node (ref "LED11") (pin "3") (pinfunction "DO_3") (pintype "output"))
      (node (ref "LED12") (pin "1") (pinfunction "DI_1") (pintype "input"))
    )
    (net (code "51") (name "Net-(U1-3V3_EN-Pad37)") (class "Default")
      (node (ref "U1") (pin "37") (pinfunction "3V3_EN_37") (pintype "input"))
      (node (ref "U1") (pin "P$37") (pinfunction "3V3_EN_P$37") (pintype "input"))
    )
    (net (code "52") (name "Net-(U1-ADC_REF-Pad35)") (class "Default")
      (node (ref "U1") (pin "35") (pinfunction "ADC_REF_35") (pintype "input"))
      (node (ref "U1") (pin "P$35") (pinfunction "ADC_REF_P$35") (pintype "input"))
    )
    (net (code "53") (name "Net-(U1-RUN-Pad30)") (class "Default")
      (node (ref "U1") (pin "30") (pinfunction "RUN_30") (pintype "input"))
      (node (ref "U1") (pin "P$30") (pinfunction "RUN_P$30") (pintype "input"))
    )
    (net (code "54") (name "Net-(U1-VBUS-Pad40)") (class "Default")
      (node (ref "U1") (pin "40") (pinfunction "VBUS_40") (pintype "power_in"))
      (node (ref "U1") (pin "P$40") (pinfunction "VBUS_P$40") (pintype "power_in"))
    )
    (net (code "55") (name "Net-(U1-VSYS-Pad39)") (class "Default")
      (node (ref "U1") (pin "39") (pinfunction "VSYS_39") (pintype "power_in"))
      (node (ref "U1") (pin "P$39") (pinfunction "VSYS_P$39") (pintype "power_in"))
    )
    (net (code "56") (name "Net-(U6-A)") (class "Default")
      (node (ref "D1") (pin "C") (pinfunction "C_C") (pintype "passive"))
      (node (ref "R9") (pin "1") (pinfunction "1_1") (pintype "passive"))
      (node (ref "U6") (pin "1") (pinfunction "A_1") (pintype "passive"))
    )
    (net (code "57") (name "Net-(U6-C)") (class "Default")
      (node (ref "D1") (pin "A") (pinfunction "A_A") (pintype "passive"))
      (node (ref "J2") (pin "TIP") (pinfunction "TIP_TIP") (pintype "bidirectional"))
      (node (ref "U6") (pin "2") (pinfunction "C_2") (pintype "passive"))
    )
    (net (code "58") (name "unconnected-(J1-PadRING2)") (class "Default")
      (node (ref "J1") (pin "RING2") (pinfunction "RING2_RING2") (pintype "bidirectional"))
    )
    (net (code "59") (name "unconnected-(J2-PadRING2)") (class "Default")
      (node (ref "J2") (pin "RING2") (pinfunction "RING2_RING2") (pintype "bidirectional"))
    )
    (net (code "60") (name "unconnected-(LED12-DO-Pad3)") (class "Default")
      (node (ref "LED12") (pin "3") (pinfunction "DO_3") (pintype "output"))
    )
    (net (code "61") (name "unconnected-(PCM5102A-Pad1)") (class "Default")
      (node (ref "PCM5102A") (pin "1") (pinfunction "1_1") (pintype "bidirectional"))
    )
    (net (code "62") (name "unconnected-(PCM5102A-Pad2)") (class "Default")
      (node (ref "PCM5102A") (pin "2") (pinfunction "2_2") (pintype "bidirectional"))
    )
    (net (code "63") (name "unconnected-(PCM5102A-Pad3)") (class "Default")
      (node (ref "PCM5102A") (pin "3") (pinfunction "3_3") (pintype "bidirectional"))
    )
    (net (code "64") (name "unconnected-(PCM5102A-Pad4)") (class "Default")
      (node (ref "PCM5102A") (pin "4") (pinfunction "4_4") (pintype "bidirectional"))
    )
    (net (code "65") (name "unconnected-(PCM5102A-Pad5)") (class "Default")
      (node (ref "PCM5102A") (pin "5") (pinfunction "5_5") (pintype "bidirectional"))
    )
    (net (code "66") (name "unconnected-(PCM5102A-PadG1)") (class "Default")
      (node (ref "PCM5102A") (pin "G1") (pinfunction "G1_G1") (pintype "bidirectional"))
    )
    (net (code "67") (name "unconnected-(PCM5102A-PadG2)") (class "Default")
      (node (ref "PCM5102A") (pin "G2") (pinfunction "G2_G2") (pintype "bidirectional"))
    )
    (net (code "68") (name "unconnected-(PCM5102A-PadL)") (class "Default")
      (node (ref "PCM5102A") (pin "L") (pinfunction "L_L") (pintype "bidirectional"))
    )
    (net (code "69") (name "unconnected-(PCM5102A-PadR)") (class "Default")
      (node (ref "PCM5102A") (pin "R") (pinfunction "R_R") (pintype "bidirectional"))
    )
  )
)
